# Power_Conversion.net
KiCad netlist of a schematic drawn in Altium Designer
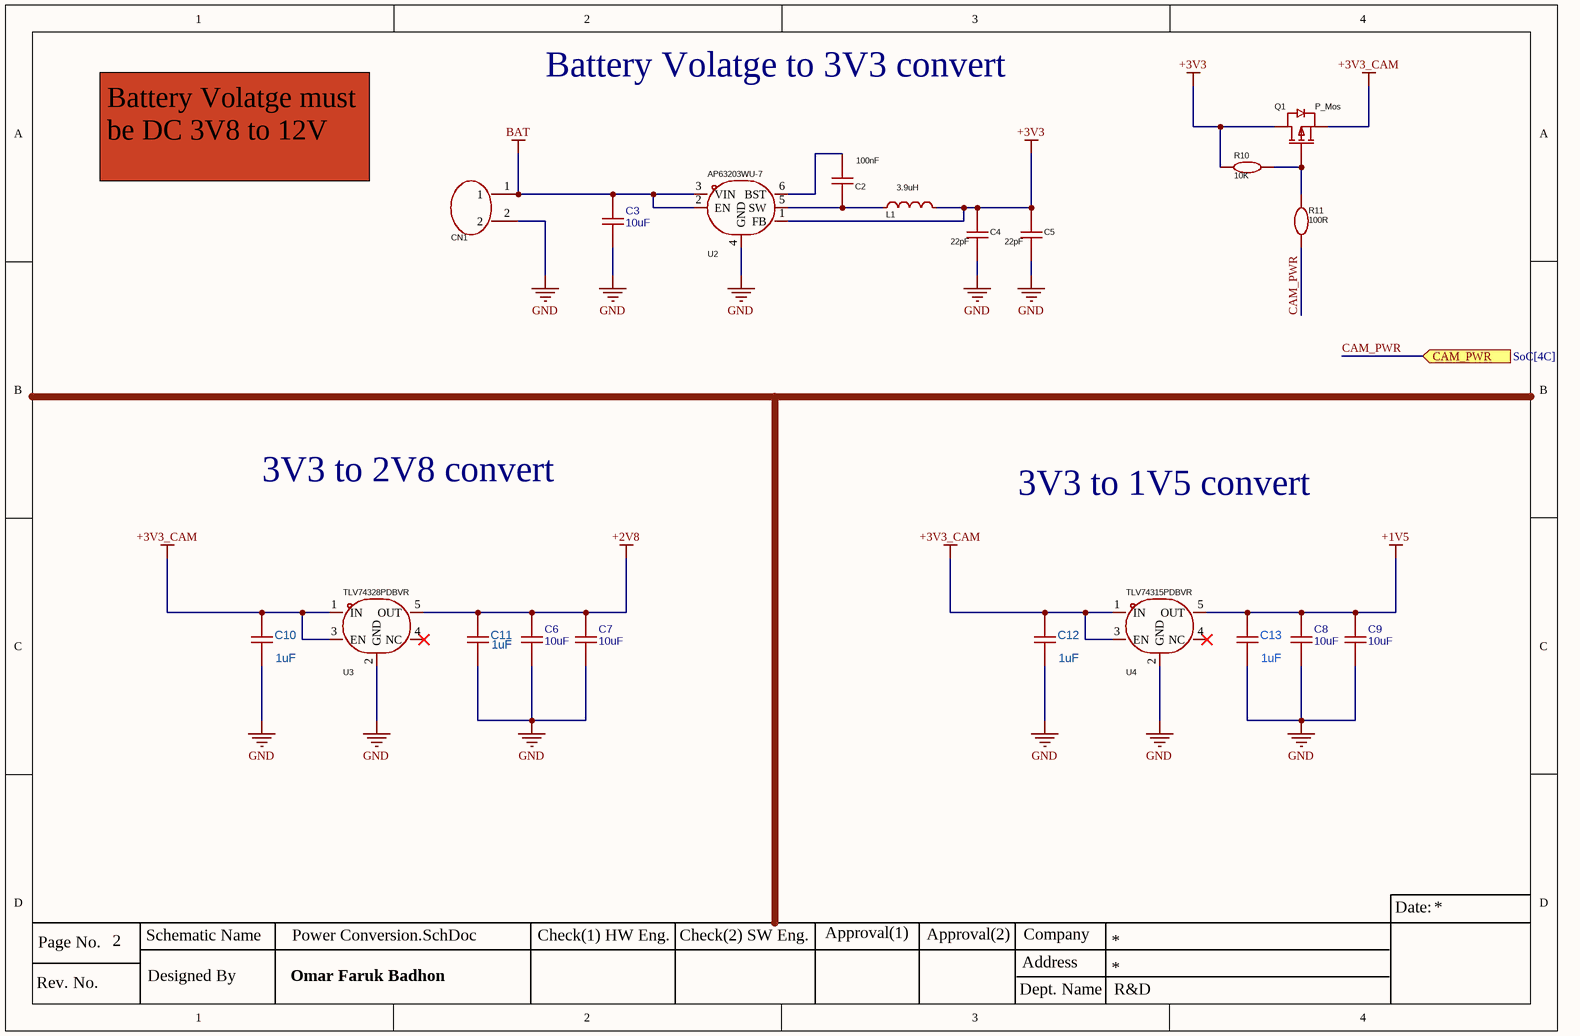
[diagram p0: Power Conversion.SchDoc]

(export (version "E")
  (design (tool "Eeschema 10.0.6"))
  (components
    (comp (ref "C2")
      (value "100nF")
      (footprint "100nF SMD Ceramic 201")
      (description "10V 100nF X5R ±10% 0201 Multilayer Ceramic Capacitors MLCC - SMD/SMT ROHS")
      (fields
        (field (name "MANUFACTURER") "muRata(村田)")
        (field (name "MANUFACTURER PART") "GRM033R61A104KE84D")
      )
      (libsource (lib "Esp32 CAM SCH") (part "100nF SMD Ceramic 201"))
    )
    (comp (ref "C3")
      (value "10uF")
      (footprint "10uF SMD Ceramic 603")
      (description "10V 10uF B ±10% 0603 Multilayer Ceramic Capacitors MLCC - SMD/SMT ROHS")
      (fields
        (field (name "MANUFACTURER") "muRata(村田)")
        (field (name "MANUFACTURER PART") "GRM188B31A106KE69D")
        (field (name "CONTRIBUTOR") "LCSC")
      )
      (libsource (lib "Esp32 CAM SCH") (part "10uF SMD Ceramic 603"))
    )
    (comp (ref "C4")
      (value "22pF")
      (footprint "22pF SMD Ceramic 603")
      (description "16V 22pF C0G ±5% 0603 Multilayer Ceramic Capacitors MLCC - SMD/SMT ROHS")
      (fields
        (field (name "MANUFACTURER") "KEMET(基美)")
        (field (name "MANUFACTURER PART") "C0603C220J4GAC7867")
      )
      (libsource (lib "Esp32 CAM SCH") (part "22pF SMD Ceramic 603"))
    )
    (comp (ref "C5")
      (value "22pF")
      (footprint "22pF SMD Ceramic 603")
      (description "16V 22pF C0G ±5% 0603 Multilayer Ceramic Capacitors MLCC - SMD/SMT ROHS")
      (fields
        (field (name "MANUFACTURER") "KEMET(基美)")
        (field (name "MANUFACTURER PART") "C0603C220J4GAC7867")
      )
      (libsource (lib "Esp32 CAM SCH") (part "22pF SMD Ceramic 603"))
    )
    (comp (ref "C6")
      (value "10uF")
      (footprint "10uF SMD Ceramic 603")
      (description "10V 10uF B ±10% 0603 Multilayer Ceramic Capacitors MLCC - SMD/SMT ROHS")
      (fields
        (field (name "MANUFACTURER") "muRata(村田)")
        (field (name "MANUFACTURER PART") "GRM188B31A106KE69D")
        (field (name "CONTRIBUTOR") "LCSC")
      )
      (libsource (lib "Esp32 CAM SCH") (part "10uF SMD Ceramic 603"))
    )
    (comp (ref "C7")
      (value "10uF")
      (footprint "10uF SMD Ceramic 603")
      (description "10V 10uF B ±10% 0603 Multilayer Ceramic Capacitors MLCC - SMD/SMT ROHS")
      (fields
        (field (name "MANUFACTURER") "muRata(村田)")
        (field (name "MANUFACTURER PART") "GRM188B31A106KE69D")
        (field (name "CONTRIBUTOR") "LCSC")
      )
      (libsource (lib "Esp32 CAM SCH") (part "10uF SMD Ceramic 603"))
    )
    (comp (ref "C8")
      (value "10uF")
      (footprint "10uF SMD Ceramic 603")
      (description "10V 10uF B ±10% 0603 Multilayer Ceramic Capacitors MLCC - SMD/SMT ROHS")
      (fields
        (field (name "MANUFACTURER") "muRata(村田)")
        (field (name "MANUFACTURER PART") "GRM188B31A106KE69D")
        (field (name "CONTRIBUTOR") "LCSC")
      )
      (libsource (lib "Esp32 CAM SCH") (part "10uF SMD Ceramic 603"))
    )
    (comp (ref "C9")
      (value "10uF")
      (footprint "10uF SMD Ceramic 603")
      (description "10V 10uF B ±10% 0603 Multilayer Ceramic Capacitors MLCC - SMD/SMT ROHS")
      (fields
        (field (name "MANUFACTURER") "muRata(村田)")
        (field (name "MANUFACTURER PART") "GRM188B31A106KE69D")
        (field (name "CONTRIBUTOR") "LCSC")
      )
      (libsource (lib "Esp32 CAM SCH") (part "10uF SMD Ceramic 603"))
    )
    (comp (ref "C10")
      (value "1uF")
      (footprint "1uF Cap")
      (description "16V 1uF Y5V -20%~+80% 0603 Multilayer Ceramic Capacitors MLCC - SMD/SMT ROHS")
      (fields
        (field (name "MANUFACTURER") "SAMWHA(三和)")
        (field (name "MANUFACTURER PART") "CS1608Y5V105Z160NRB")
      )
      (libsource (lib "Esp32 CAM SCH") (part "1uF Ceramic SMD 603"))
    )
    (comp (ref "C11")
      (value "1uF")
      (footprint "1uF Cap")
      (description "16V 1uF Y5V -20%~+80% 0603 Multilayer Ceramic Capacitors MLCC - SMD/SMT ROHS")
      (fields
        (field (name "MANUFACTURER") "SAMWHA(三和)")
        (field (name "MANUFACTURER PART") "CS1608Y5V105Z160NRB")
      )
      (libsource (lib "Esp32 CAM SCH") (part "1uF Ceramic SMD 603"))
    )
    (comp (ref "C12")
      (value "1uF")
      (footprint "1uF Cap")
      (description "16V 1uF Y5V -20%~+80% 0603 Multilayer Ceramic Capacitors MLCC - SMD/SMT ROHS")
      (fields
        (field (name "MANUFACTURER") "SAMWHA(三和)")
        (field (name "MANUFACTURER PART") "CS1608Y5V105Z160NRB")
      )
      (libsource (lib "Esp32 CAM SCH") (part "1uF Ceramic SMD 603"))
    )
    (comp (ref "C13")
      (value "1uF")
      (footprint "1uF Cap")
      (description "16V 1uF Y5V -20%~+80% 0603 Multilayer Ceramic Capacitors MLCC - SMD/SMT ROHS")
      (fields
        (field (name "MANUFACTURER") "SAMWHA(三和)")
        (field (name "MANUFACTURER PART") "CS1608Y5V105Z160NRB")
      )
      (libsource (lib "Esp32 CAM SCH") (part "1uF Ceramic SMD 603"))
    )
    (comp (ref "CN1")
      (value "B2B-PH-K-S(LF)(SN)")
      (footprint "Connector 2P")
      (description "1x2P 2P PH Tin 2 -25℃~+85℃ 2A 1 2mm Brass Direct Insert Plugin,P=2mm Wire To Board Connector ROHS")
      (fields (field (name "MANUFACTURER") "JST"))
      (libsource (lib "Esp32 CAM SCH") (part "Connector 2P"))
    )
    (comp (ref "L1")
      (value "3.9uH")
      (footprint "3.9uH power Inductor")
      (description "1.5A 3.9uH ±20% 1.4A SMD,3x3mm Power Inductors ROHS")
      (fields (field (name "MANUFACTURER") "cjiang(长江微电)") (field (name "MANUFACTURER PART") "FNR3015S3R9MT"))
      (libsource (lib "Esp32 CAM SCH") (part "3.9uH SMD PI"))
    )
    (comp (ref "Q1")
      (value "P_Mos")
      (footprint "P channel msfet (AO3401A1)")
      (description "30V 4A 44mΩ@10V,4.3A 1.4W 1.3V@250uA 1 Piece P-Channel SOT-23 MOSFETs ROHS")
      (fields (field (name "MANUFACTURER") "AOS") (field (name "MANUFACTURER PART") "AO3401A"))
      (libsource (lib "Esp32 CAM SCH") (part "P channel msfet (AO3401A1)"))
    )
    (comp (ref "R10")
      (value "10K")
      (footprint "10K SMD Ceramic 201")
      (description "50mW Thick Film Resistors 25V ±1% ±200ppm/℃ 10kΩ 0201 Chip Resistor - Surface Mount ROHS")
      (fields (field (name "MANUFACTURER") "YAGEO(国巨)") (field (name "MANUFACTURER PART") "AF0201FR-0710KL"))
      (libsource (lib "Esp32 CAM SCH") (part "10K SMD Ceramic 201"))
    )
    (comp (ref "R11")
      (value "100R")
      (footprint "100R 402")
      (description "100mW Thick Film Resistors ±100ppm/℃ ±1% 100Ω 0402 Chip Resistor - Surface Mount ROHS")
      (fields (field (name "MANUFACTURER") "PANASONIC(松下)") (field (name "MANUFACTURER PART") "ERJ2RKF1000X"))
      (libsource (lib "Esp32 CAM SCH") (part "100R 402"))
    )
    (comp (ref "U2")
      (value "AP63203WU-7")
      (footprint "3V3 Converter (AP63203)")
      (description "Step-down type Fixed 2A 3.3V 3.8V~32V TSOT-23-6 DC-DC Converters ROHS")
      (fields (field (name "MANUFACTURER") "DIODES(美台)"))
      (libsource (lib "Esp32 CAM SCH") (part "AP63203"))
    )
    (comp (ref "U3")
      (value "TLV74328PDBVR")
      (footprint "2V8 Converter (TLV74328)")
      (fields (field (name "MANUFACTURER") "TI(德州仪器)"))
      (libsource (lib "Esp32 CAM SCH") (part "TLV74328"))
    )
    (comp (ref "U4")
      (value "TLV74315PDBVR")
      (footprint "1V5 Converter (TLV74215)")
      (fields (field (name "MANUFACTURER") "TI(德州仪器)"))
      (libsource (lib "Esp32 CAM SCH") (part "TLV74315"))
    )
  )
  (nets
    (net (code "1") (name "+1V5") (class "Default")
      (node (ref "C13") (pin "2") (pinfunction "2_2") (pintype "passive"))
      (node (ref "C8") (pin "2") (pinfunction "2_2") (pintype "passive"))
      (node (ref "C9") (pin "2") (pinfunction "2_2") (pintype "passive"))
      (node (ref "U4") (pin "5") (pinfunction "OUT_5") (pintype "passive"))
    )
    (net (code "2") (name "+2V8") (class "Default")
      (node (ref "C11") (pin "2") (pinfunction "2_2") (pintype "passive"))
      (node (ref "C6") (pin "2") (pinfunction "2_2") (pintype "passive"))
      (node (ref "C7") (pin "2") (pinfunction "2_2") (pintype "passive"))
      (node (ref "U3") (pin "5") (pinfunction "OUT_5") (pintype "passive"))
    )
    (net (code "3") (name "+3V3") (class "Default")
      (node (ref "C4") (pin "2") (pinfunction "2_2") (pintype "passive"))
      (node (ref "C5") (pin "2") (pinfunction "2_2") (pintype "passive"))
      (node (ref "L1") (pin "2") (pinfunction "2_2") (pintype "passive"))
      (node (ref "Q1") (pin "3") (pinfunction "D_3") (pintype "passive"))
      (node (ref "R10") (pin "1") (pinfunction "1_1") (pintype "passive"))
      (node (ref "U2") (pin "1") (pinfunction "FB_1") (pintype "passive"))
    )
    (net (code "4") (name "+3V3_CAM") (class "Default")
      (node (ref "C10") (pin "2") (pinfunction "2_2") (pintype "passive"))
      (node (ref "C12") (pin "2") (pinfunction "2_2") (pintype "passive"))
      (node (ref "Q1") (pin "2") (pinfunction "S_2") (pintype "passive"))
      (node (ref "U3") (pin "1") (pinfunction "IN_1") (pintype "passive"))
      (node (ref "U3") (pin "3") (pinfunction "EN_3") (pintype "passive"))
      (node (ref "U4") (pin "1") (pinfunction "IN_1") (pintype "passive"))
      (node (ref "U4") (pin "3") (pinfunction "EN_3") (pintype "passive"))
    )
    (net (code "5") (name "/CAM_PWR") (class "Default")
      (node (ref "R11") (pin "1") (pinfunction "1_1") (pintype "passive"))
    )
    (net (code "6") (name "BAT") (class "Default")
      (node (ref "C3") (pin "2") (pinfunction "2_2") (pintype "passive"))
      (node (ref "CN1") (pin "1") (pinfunction "1_1") (pintype "passive"))
      (node (ref "U2") (pin "2") (pinfunction "EN_2") (pintype "passive"))
      (node (ref "U2") (pin "3") (pinfunction "VIN_3") (pintype "passive"))
    )
    (net (code "7") (name "GND") (class "Default")
      (node (ref "C10") (pin "1") (pinfunction "1_1") (pintype "passive"))
      (node (ref "C11") (pin "1") (pinfunction "1_1") (pintype "passive"))
      (node (ref "C12") (pin "1") (pinfunction "1_1") (pintype "passive"))
      (node (ref "C13") (pin "1") (pinfunction "1_1") (pintype "passive"))
      (node (ref "C3") (pin "1") (pinfunction "1_1") (pintype "passive"))
      (node (ref "C4") (pin "1") (pinfunction "1_1") (pintype "passive"))
      (node (ref "C5") (pin "1") (pinfunction "1_1") (pintype "passive"))
      (node (ref "C6") (pin "1") (pinfunction "1_1") (pintype "passive"))
      (node (ref "C7") (pin "1") (pinfunction "1_1") (pintype "passive"))
      (node (ref "C8") (pin "1") (pinfunction "1_1") (pintype "passive"))
      (node (ref "C9") (pin "1") (pinfunction "1_1") (pintype "passive"))
      (node (ref "CN1") (pin "2") (pinfunction "2_2") (pintype "passive"))
      (node (ref "U2") (pin "4") (pinfunction "GND_4") (pintype "passive"))
      (node (ref "U3") (pin "2") (pinfunction "GND_2") (pintype "passive"))
      (node (ref "U4") (pin "2") (pinfunction "GND_2") (pintype "passive"))
    )
    (net (code "8") (name "Net-(Q1-G)") (class "Default")
      (node (ref "Q1") (pin "1") (pinfunction "G_1") (pintype "passive"))
      (node (ref "R10") (pin "2") (pinfunction "2_2") (pintype "passive"))
      (node (ref "R11") (pin "2") (pinfunction "2_2") (pintype "passive"))
    )
    (net (code "9") (name "Net-(U2-BST)") (class "Default")
      (node (ref "C2") (pin "2") (pinfunction "2_2") (pintype "passive"))
      (node (ref "U2") (pin "6") (pinfunction "BST_6") (pintype "passive"))
    )
    (net (code "10") (name "Net-(U2-SW)") (class "Default")
      (node (ref "C2") (pin "1") (pinfunction "1_1") (pintype "passive"))
      (node (ref "L1") (pin "1") (pinfunction "1_1") (pintype "passive"))
      (node (ref "U2") (pin "5") (pinfunction "SW_5") (pintype "passive"))
    )
    (net (code "11") (name "unconnected-(U3-NC-Pad4)") (class "Default")
      (node (ref "U3") (pin "4") (pinfunction "NC_4") (pintype "passive+no_connect"))
    )
    (net (code "12") (name "unconnected-(U4-NC-Pad4)") (class "Default")
      (node (ref "U4") (pin "4") (pinfunction "NC_4") (pintype "passive+no_connect"))
    )
  )
)
